# MesschieberBackup.net
KiCad netlist of a schematic drawn in EAGLE
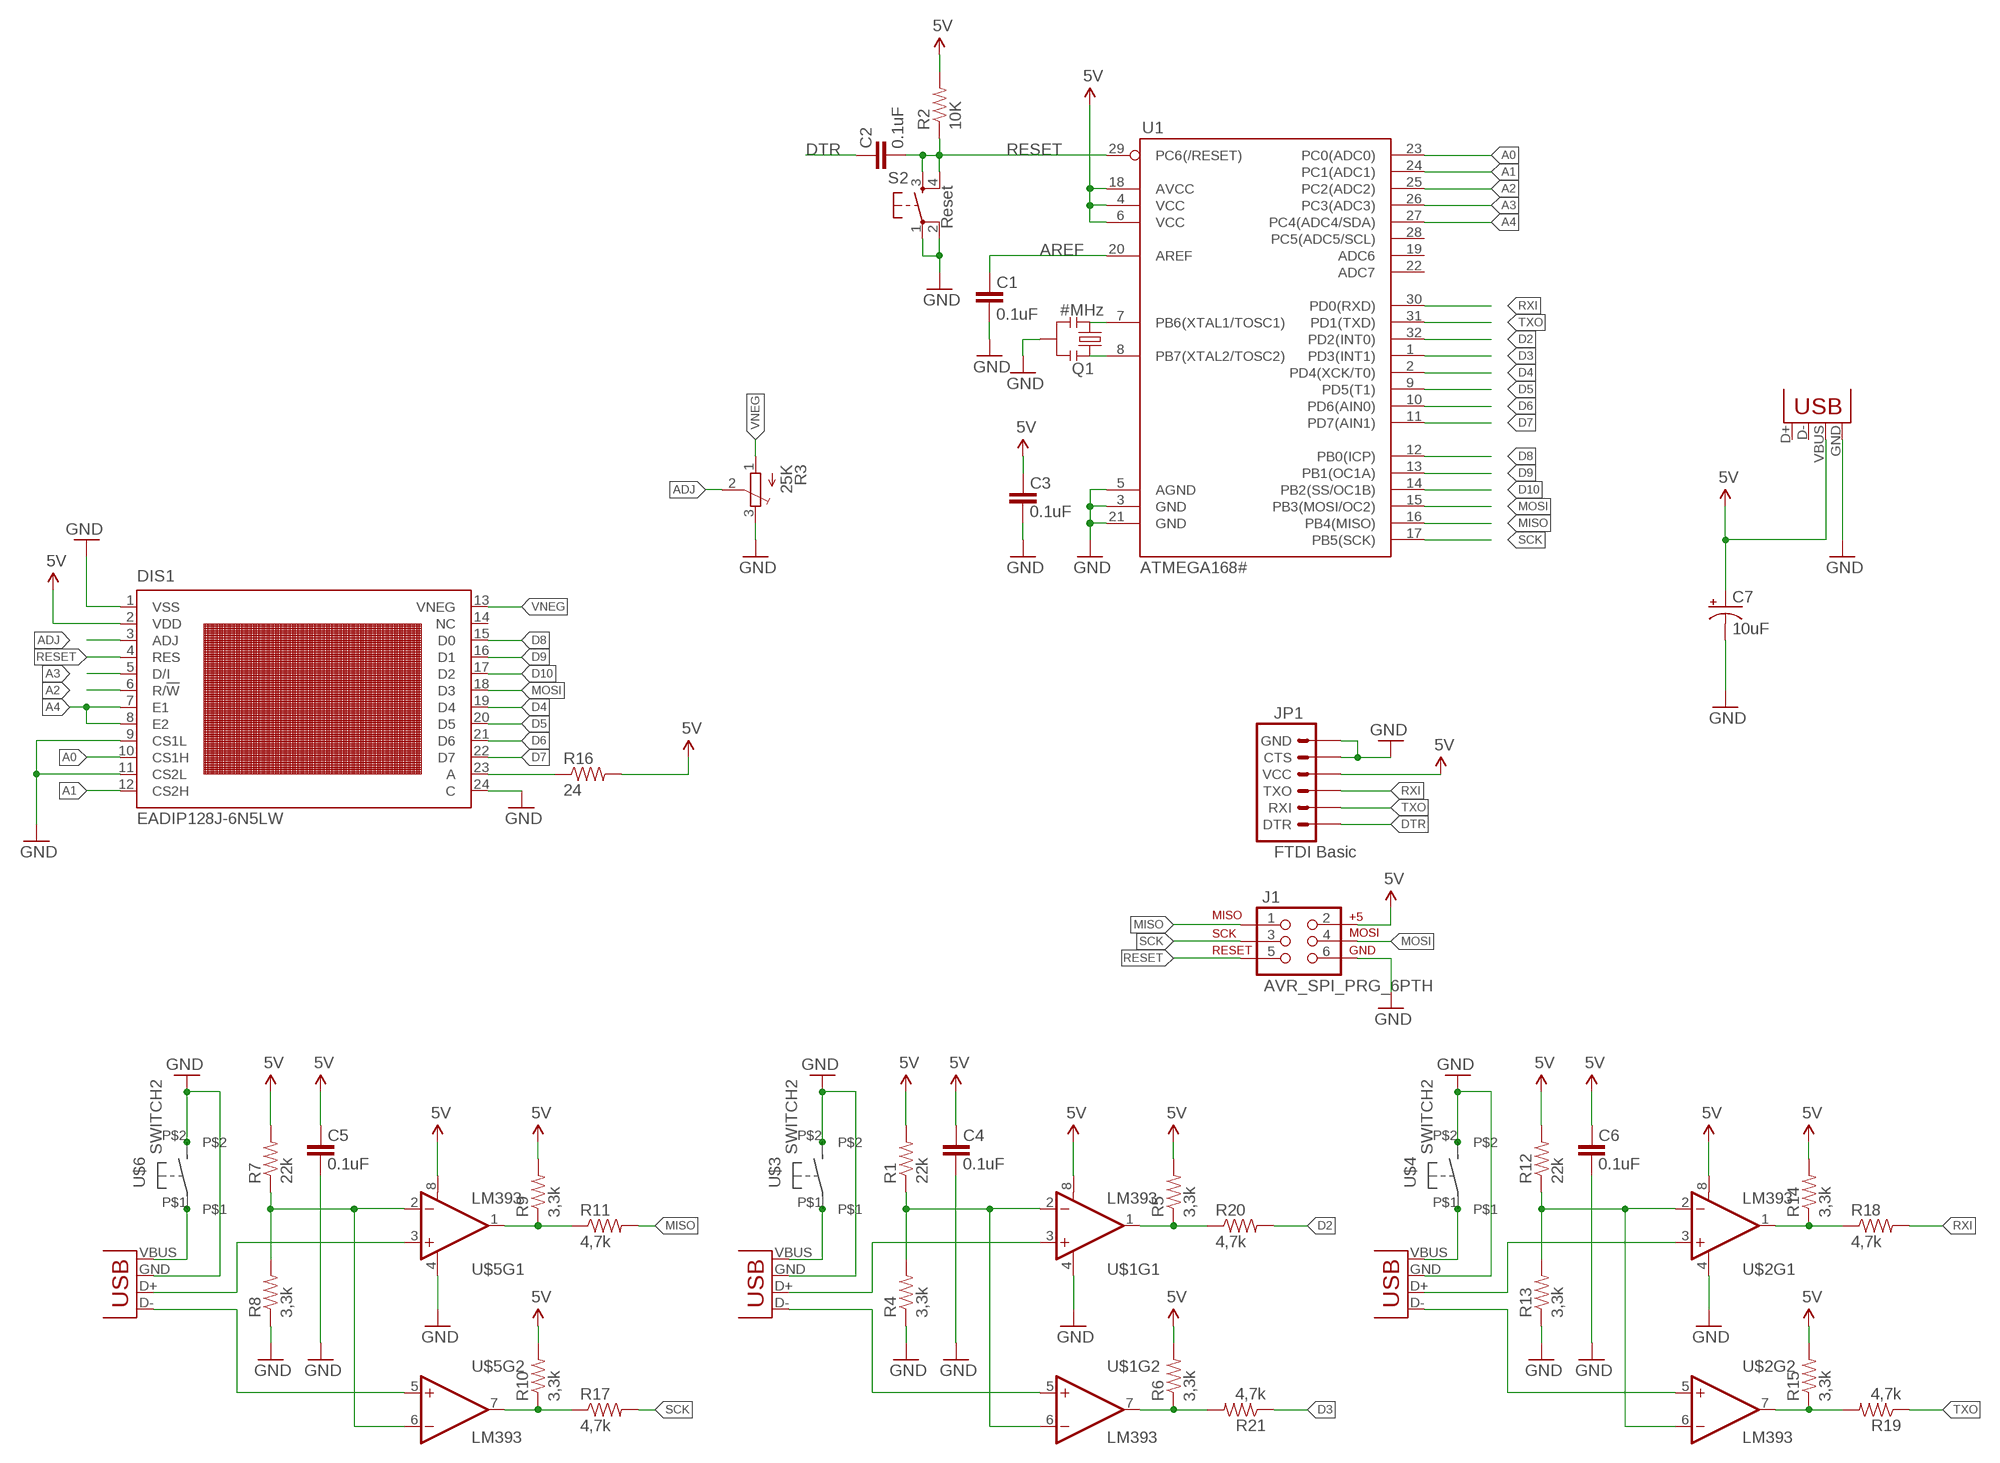
[diagram p0: schematic, sheet 1]

(export (version "E")
  (design (tool "Eeschema 10.0.6"))
  (components
    (comp (ref "C1")
      (value "0.1uF")
      (footprint "eagle-import:0805")
      (libsource (lib "eagle-import") (part "CAP0805"))
    )
    (comp (ref "C2")
      (value "0.1uF")
      (footprint "eagle-import:0805")
      (libsource (lib "eagle-import") (part "CAP0805"))
    )
    (comp (ref "C3")
      (value "0.1uF")
      (footprint "eagle-import:0805")
      (libsource (lib "eagle-import") (part "CAP0805"))
    )
    (comp (ref "C4")
      (value "0.1uF")
      (footprint "eagle-import:0805")
      (libsource (lib "eagle-import") (part "CAP0805"))
    )
    (comp (ref "C5")
      (value "0.1uF")
      (footprint "eagle-import:0805")
      (libsource (lib "eagle-import") (part "CAP0805"))
    )
    (comp (ref "C6")
      (value "0.1uF")
      (footprint "eagle-import:0805")
      (libsource (lib "eagle-import") (part "CAP0805"))
    )
    (comp (ref "C7")
      (value "10uF")
      (footprint "eagle-import:EIA3216")
      (libsource (lib "eagle-import") (part "10UF-16V-10%(TANT)"))
    )
    (comp (ref "DIS1")
      (value "EADIP128J-6N5LW")
      (footprint "eagle-import:LCD-DIP128-64")
      (libsource (lib "eagle-import") (part "EADIP128-6N5LWJ"))
    )
    (comp (ref "J1")
      (value "AVR_SPI_PRG_6PTH")
      (footprint "eagle-import:2X3")
      (libsource (lib "eagle-import") (part "AVR_SPI_PRG_6PTH"))
    )
    (comp (ref "JP1")
      (value "FTDI Basic")
      (footprint "eagle-import:1X06")
      (libsource (lib "eagle-import") (part "ARDUINO_SERIAL_PROGRAMPTH"))
    )
    (comp (ref "JP2")
      (value "USB-A-H")
      (footprint "eagle-import:USB-A-H")
      (libsource (lib "eagle-import") (part "USB-A-H"))
    )
    (comp (ref "JP3")
      (value "USB-A-H")
      (footprint "eagle-import:USB-A-H")
      (libsource (lib "eagle-import") (part "USB-A-H"))
    )
    (comp (ref "JP6")
      (value "USB-A-H")
      (footprint "eagle-import:USB-A-H")
      (libsource (lib "eagle-import") (part "USB-A-H"))
    )
    (comp (ref "JP7")
      (value "USB-SMD-NS")
      (footprint "eagle-import:USB-MINIB-NOSTOP")
      (libsource (lib "eagle-import") (part "USB-SMD-NS"))
    )
    (comp (ref "Q1")
      (value "#MHz")
      (footprint "eagle-import:RESONATOR-SMD")
      (libsource (lib "eagle-import") (part "RESONATORSMD"))
    )
    (comp (ref "R1")
      (value "22k")
      (footprint "eagle-import:0805")
      (libsource (lib "eagle-import") (part "RESISTOR"))
    )
    (comp (ref "R2")
      (value "10K")
      (footprint "eagle-import:0805")
      (libsource (lib "eagle-import") (part "RESISTOR"))
    )
    (comp (ref "R3")
      (value "25K")
      (footprint "eagle-import:SM-42_43A")
      (libsource (lib "eagle-import") (part "TRIM_EU-SM-42/43A"))
    )
    (comp (ref "R4")
      (value "3,3k")
      (footprint "eagle-import:0805")
      (libsource (lib "eagle-import") (part "RESISTOR"))
    )
    (comp (ref "R5")
      (value "3,3k")
      (footprint "eagle-import:0805")
      (libsource (lib "eagle-import") (part "RESISTOR"))
    )
    (comp (ref "R6")
      (value "3,3k")
      (footprint "eagle-import:0805")
      (libsource (lib "eagle-import") (part "RESISTOR"))
    )
    (comp (ref "R7")
      (value "22k")
      (footprint "eagle-import:0805")
      (libsource (lib "eagle-import") (part "RESISTOR"))
    )
    (comp (ref "R8")
      (value "3,3k")
      (footprint "eagle-import:0805")
      (libsource (lib "eagle-import") (part "RESISTOR"))
    )
    (comp (ref "R9")
      (value "3,3k")
      (footprint "eagle-import:0805")
      (libsource (lib "eagle-import") (part "RESISTOR"))
    )
    (comp (ref "R10")
      (value "3,3k")
      (footprint "eagle-import:0805")
      (libsource (lib "eagle-import") (part "RESISTOR"))
    )
    (comp (ref "R11")
      (value "4,7k")
      (footprint "eagle-import:0805")
      (libsource (lib "eagle-import") (part "RESISTOR"))
    )
    (comp (ref "R12")
      (value "22k")
      (footprint "eagle-import:0805")
      (libsource (lib "eagle-import") (part "RESISTOR"))
    )
    (comp (ref "R13")
      (value "3,3k")
      (footprint "eagle-import:0805")
      (libsource (lib "eagle-import") (part "RESISTOR"))
    )
    (comp (ref "R14")
      (value "3,3k")
      (footprint "eagle-import:0805")
      (libsource (lib "eagle-import") (part "RESISTOR"))
    )
    (comp (ref "R15")
      (value "3,3k")
      (footprint "eagle-import:0805")
      (libsource (lib "eagle-import") (part "RESISTOR"))
    )
    (comp (ref "R16")
      (value "24")
      (footprint "eagle-import:0805")
      (libsource (lib "eagle-import") (part "RESISTOR"))
    )
    (comp (ref "R17")
      (value "4,7k")
      (footprint "eagle-import:0805")
      (libsource (lib "eagle-import") (part "RESISTOR"))
    )
    (comp (ref "R18")
      (value "4,7k")
      (footprint "eagle-import:0805")
      (libsource (lib "eagle-import") (part "RESISTOR"))
    )
    (comp (ref "R19")
      (value "4,7k")
      (footprint "eagle-import:0805")
      (libsource (lib "eagle-import") (part "RESISTOR"))
    )
    (comp (ref "R20")
      (value "4,7k")
      (footprint "eagle-import:0805")
      (libsource (lib "eagle-import") (part "RESISTOR"))
    )
    (comp (ref "R21")
      (value "4,7k")
      (footprint "eagle-import:0805")
      (libsource (lib "eagle-import") (part "RESISTOR"))
    )
    (comp (ref "S2")
      (value "Reset")
      (footprint "eagle-import:TACTILE_SWITCH_SMD")
      (libsource (lib "eagle-import") (part "TAC_SWITCHSND"))
    )
    (comp (ref "U$1")
      (value "LM393")
      (footprint "eagle-import:SO08")
      (libsource (lib "eagle-import") (part "LM393"))
    )
    (comp (ref "U$2")
      (value "LM393")
      (footprint "eagle-import:SO08")
      (libsource (lib "eagle-import") (part "LM393"))
    )
    (comp (ref "U$3")
      (value "SWITCH2")
      (footprint "eagle-import:SWITCH2")
      (libsource (lib "eagle-import") (part "SWITCH2"))
    )
    (comp (ref "U$4")
      (value "SWITCH2")
      (footprint "eagle-import:SWITCH2")
      (libsource (lib "eagle-import") (part "SWITCH2"))
    )
    (comp (ref "U$5")
      (value "LM393")
      (footprint "eagle-import:SO08")
      (libsource (lib "eagle-import") (part "LM393"))
    )
    (comp (ref "U$6")
      (value "SWITCH2")
      (footprint "eagle-import:SWITCH2")
      (libsource (lib "eagle-import") (part "SWITCH2"))
    )
    (comp (ref "U1")
      (value "ATMEGA168#")
      (footprint "eagle-import:TQFP32-08")
      (libsource (lib "eagle-import") (part "ATMEGA168"))
    )
  )
  (nets
    (net (code "1") (name "/AREF") (class "Default")
      (node (ref "C1") (pin "2") (pinfunction "2_2") (pintype "passive"))
      (node (ref "U1") (pin "20") (pinfunction "AREF_20") (pintype "bidirectional"))
    )
    (net (code "2") (name "5V") (class "Default")
      (node (ref "C3") (pin "2") (pinfunction "2_2") (pintype "passive"))
      (node (ref "C4") (pin "2") (pinfunction "2_2") (pintype "passive"))
      (node (ref "C5") (pin "2") (pinfunction "2_2") (pintype "passive"))
      (node (ref "C6") (pin "2") (pinfunction "2_2") (pintype "passive"))
      (node (ref "C7") (pin "A") (pinfunction "+_A") (pintype "passive"))
      (node (ref "DIS1") (pin "2") (pinfunction "VDD_2") (pintype "power_in"))
      (node (ref "J1") (pin "2") (pinfunction "2_2") (pintype "passive"))
      (node (ref "JP1") (pin "4") (pinfunction "VCC_4") (pintype "passive"))
      (node (ref "JP7") (pin "VBUS") (pinfunction "VBUS_VBUS") (pintype "bidirectional"))
      (node (ref "R1") (pin "2") (pinfunction "2_2") (pintype "passive"))
      (node (ref "R10") (pin "2") (pinfunction "2_2") (pintype "passive"))
      (node (ref "R12") (pin "2") (pinfunction "2_2") (pintype "passive"))
      (node (ref "R14") (pin "2") (pinfunction "2_2") (pintype "passive"))
      (node (ref "R15") (pin "2") (pinfunction "2_2") (pintype "passive"))
      (node (ref "R16") (pin "2") (pinfunction "2_2") (pintype "passive"))
      (node (ref "R2") (pin "2") (pinfunction "2_2") (pintype "passive"))
      (node (ref "R5") (pin "2") (pinfunction "2_2") (pintype "passive"))
      (node (ref "R6") (pin "2") (pinfunction "2_2") (pintype "passive"))
      (node (ref "R7") (pin "2") (pinfunction "2_2") (pintype "passive"))
      (node (ref "R9") (pin "2") (pinfunction "2_2") (pintype "passive"))
      (node (ref "U$1") (pin "8") (pinfunction "V+_8") (pintype "power_in"))
      (node (ref "U$2") (pin "8") (pinfunction "V+_8") (pintype "power_in"))
      (node (ref "U$5") (pin "8") (pinfunction "V+_8") (pintype "power_in"))
      (node (ref "U1") (pin "18") (pinfunction "AVCC_18") (pintype "bidirectional"))
      (node (ref "U1") (pin "4") (pinfunction "VCC_4") (pintype "bidirectional"))
      (node (ref "U1") (pin "6") (pinfunction "VCC_6") (pintype "bidirectional"))
    )
    (net (code "3") (name "A0") (class "Default")
      (node (ref "DIS1") (pin "10") (pinfunction "CS1H_10") (pintype "input"))
      (node (ref "U1") (pin "23") (pinfunction "PC0(ADC0)_23") (pintype "bidirectional"))
    )
    (net (code "4") (name "A1") (class "Default")
      (node (ref "DIS1") (pin "12") (pinfunction "CS2H_12") (pintype "input"))
      (node (ref "U1") (pin "24") (pinfunction "PC1(ADC1)_24") (pintype "bidirectional"))
    )
    (net (code "5") (name "A2") (class "Default")
      (node (ref "DIS1") (pin "6") (pinfunction "R/~{W}_6") (pintype "input"))
      (node (ref "U1") (pin "25") (pinfunction "PC2(ADC2)_25") (pintype "bidirectional"))
    )
    (net (code "6") (name "A3") (class "Default")
      (node (ref "DIS1") (pin "5") (pinfunction "D/I_5") (pintype "input"))
      (node (ref "U1") (pin "26") (pinfunction "PC3(ADC3)_26") (pintype "bidirectional"))
    )
    (net (code "7") (name "A4") (class "Default")
      (node (ref "DIS1") (pin "7") (pinfunction "E1_7") (pintype "input"))
      (node (ref "DIS1") (pin "8") (pinfunction "E2_8") (pintype "input"))
      (node (ref "U1") (pin "27") (pinfunction "PC4(ADC4/SDA)_27") (pintype "bidirectional"))
    )
    (net (code "8") (name "ADJ") (class "Default")
      (node (ref "DIS1") (pin "3") (pinfunction "ADJ_3") (pintype "input"))
      (node (ref "R3") (pin "2") (pinfunction "S_2") (pintype "passive"))
    )
    (net (code "9") (name "D2") (class "Default")
      (node (ref "R20") (pin "2") (pinfunction "2_2") (pintype "passive"))
      (node (ref "U1") (pin "32") (pinfunction "PD2(INT0)_32") (pintype "bidirectional"))
    )
    (net (code "10") (name "D3") (class "Default")
      (node (ref "R21") (pin "1") (pinfunction "1_1") (pintype "passive"))
      (node (ref "U1") (pin "1") (pinfunction "PD3(INT1)_1") (pintype "bidirectional"))
    )
    (net (code "11") (name "D4") (class "Default")
      (node (ref "DIS1") (pin "19") (pinfunction "D4_19") (pintype "bidirectional"))
      (node (ref "U1") (pin "2") (pinfunction "PD4(XCK/T0)_2") (pintype "bidirectional"))
    )
    (net (code "12") (name "D5") (class "Default")
      (node (ref "DIS1") (pin "20") (pinfunction "D5_20") (pintype "bidirectional"))
      (node (ref "U1") (pin "9") (pinfunction "PD5(T1)_9") (pintype "bidirectional"))
    )
    (net (code "13") (name "D6") (class "Default")
      (node (ref "DIS1") (pin "21") (pinfunction "D6_21") (pintype "bidirectional"))
      (node (ref "U1") (pin "10") (pinfunction "PD6(AIN0)_10") (pintype "bidirectional"))
    )
    (net (code "14") (name "D7") (class "Default")
      (node (ref "DIS1") (pin "22") (pinfunction "D7_22") (pintype "bidirectional"))
      (node (ref "U1") (pin "11") (pinfunction "PD7(AIN1)_11") (pintype "bidirectional"))
    )
    (net (code "15") (name "D8") (class "Default")
      (node (ref "DIS1") (pin "15") (pinfunction "D0_15") (pintype "bidirectional"))
      (node (ref "U1") (pin "12") (pinfunction "PB0(ICP)_12") (pintype "bidirectional"))
    )
    (net (code "16") (name "D9") (class "Default")
      (node (ref "DIS1") (pin "16") (pinfunction "D1_16") (pintype "bidirectional"))
      (node (ref "U1") (pin "13") (pinfunction "PB1(OC1A)_13") (pintype "bidirectional"))
    )
    (net (code "17") (name "D10") (class "Default")
      (node (ref "DIS1") (pin "17") (pinfunction "D2_17") (pintype "bidirectional"))
      (node (ref "U1") (pin "14") (pinfunction "PB2(SS/OC1B)_14") (pintype "bidirectional"))
    )
    (net (code "18") (name "DTR") (class "Default")
      (node (ref "C2") (pin "2") (pinfunction "2_2") (pintype "passive"))
      (node (ref "JP1") (pin "1") (pinfunction "DTR_1") (pintype "passive"))
    )
    (net (code "19") (name "GND") (class "Default")
      (node (ref "C1") (pin "1") (pinfunction "1_1") (pintype "passive"))
      (node (ref "C3") (pin "1") (pinfunction "1_1") (pintype "passive"))
      (node (ref "C4") (pin "1") (pinfunction "1_1") (pintype "passive"))
      (node (ref "C5") (pin "1") (pinfunction "1_1") (pintype "passive"))
      (node (ref "C6") (pin "1") (pinfunction "1_1") (pintype "passive"))
      (node (ref "C7") (pin "C") (pinfunction "-_C") (pintype "passive"))
      (node (ref "DIS1") (pin "1") (pinfunction "VSS_1") (pintype "power_in"))
      (node (ref "DIS1") (pin "11") (pinfunction "CS2L_11") (pintype "input"))
      (node (ref "DIS1") (pin "24") (pinfunction "C_24") (pintype "passive"))
      (node (ref "DIS1") (pin "9") (pinfunction "CS1L_9") (pintype "input"))
      (node (ref "J1") (pin "6") (pinfunction "6_6") (pintype "passive"))
      (node (ref "JP1") (pin "5") (pinfunction "CTS_5") (pintype "passive"))
      (node (ref "JP1") (pin "6") (pinfunction "GND_6") (pintype "passive"))
      (node (ref "JP2") (pin "GND") (pinfunction "VBUS_GND") (pintype "bidirectional"))
      (node (ref "JP3") (pin "GND") (pinfunction "VBUS_GND") (pintype "bidirectional"))
      (node (ref "JP6") (pin "GND") (pinfunction "VBUS_GND") (pintype "bidirectional"))
      (node (ref "JP7") (pin "GND") (pinfunction "GND_GND") (pintype "bidirectional"))
      (node (ref "Q1") (pin "2") (pinfunction "2_2") (pintype "passive"))
      (node (ref "R13") (pin "1") (pinfunction "1_1") (pintype "passive"))
      (node (ref "R3") (pin "3") (pinfunction "E_3") (pintype "passive"))
      (node (ref "R4") (pin "1") (pinfunction "1_1") (pintype "passive"))
      (node (ref "R8") (pin "1") (pinfunction "1_1") (pintype "passive"))
      (node (ref "S2") (pin "1") (pinfunction "1_1") (pintype "passive"))
      (node (ref "S2") (pin "2") (pinfunction "2_2") (pintype "passive"))
      (node (ref "U$1") (pin "4") (pinfunction "V-_4") (pintype "power_in"))
      (node (ref "U$2") (pin "4") (pinfunction "V-_4") (pintype "power_in"))
      (node (ref "U$3") (pin "P$2") (pinfunction "P$2_P$2") (pintype "bidirectional"))
      (node (ref "U$4") (pin "P$2") (pinfunction "P$2_P$2") (pintype "bidirectional"))
      (node (ref "U$5") (pin "4") (pinfunction "V-_4") (pintype "power_in"))
      (node (ref "U$6") (pin "P$2") (pinfunction "P$2_P$2") (pintype "bidirectional"))
      (node (ref "U1") (pin "21") (pinfunction "GND_21") (pintype "bidirectional"))
      (node (ref "U1") (pin "3") (pinfunction "GND_3") (pintype "bidirectional"))
      (node (ref "U1") (pin "5") (pinfunction "AGND_5") (pintype "bidirectional"))
    )
    (net (code "20") (name "MISO") (class "Default")
      (node (ref "J1") (pin "1") (pinfunction "1_1") (pintype "passive"))
      (node (ref "R11") (pin "2") (pinfunction "2_2") (pintype "passive"))
      (node (ref "U1") (pin "16") (pinfunction "PB4(MISO)_16") (pintype "bidirectional"))
    )
    (net (code "21") (name "MOSI") (class "Default")
      (node (ref "DIS1") (pin "18") (pinfunction "D3_18") (pintype "bidirectional"))
      (node (ref "J1") (pin "4") (pinfunction "4_4") (pintype "passive"))
      (node (ref "U1") (pin "15") (pinfunction "PB3(MOSI/OC2)_15") (pintype "bidirectional"))
    )
    (net (code "22") (name "Net-(DIS1-A)") (class "Default")
      (node (ref "DIS1") (pin "23") (pinfunction "A_23") (pintype "passive"))
      (node (ref "R16") (pin "1") (pinfunction "1_1") (pintype "passive"))
    )
    (net (code "23") (name "Net-(JP2-D+)") (class "Default")
      (node (ref "JP2") (pin "D-") (pinfunction "D+_D-") (pintype "bidirectional"))
      (node (ref "U$1") (pin "5") (pinfunction "+IN_5") (pintype "input"))
    )
    (net (code "24") (name "Net-(JP2-D-)") (class "Default")
      (node (ref "JP2") (pin "D+") (pinfunction "D-_D+") (pintype "bidirectional"))
      (node (ref "U$1") (pin "3") (pinfunction "+IN_3") (pintype "input"))
    )
    (net (code "25") (name "Net-(JP2-GND)") (class "Default")
      (node (ref "JP2") (pin "VBUS") (pinfunction "GND_VBUS") (pintype "bidirectional"))
      (node (ref "U$3") (pin "P$1") (pinfunction "P$1_P$1") (pintype "bidirectional"))
    )
    (net (code "26") (name "Net-(JP3-D+)") (class "Default")
      (node (ref "JP3") (pin "D-") (pinfunction "D+_D-") (pintype "bidirectional"))
      (node (ref "U$5") (pin "5") (pinfunction "+IN_5") (pintype "input"))
    )
    (net (code "27") (name "Net-(JP3-D-)") (class "Default")
      (node (ref "JP3") (pin "D+") (pinfunction "D-_D+") (pintype "bidirectional"))
      (node (ref "U$5") (pin "3") (pinfunction "+IN_3") (pintype "input"))
    )
    (net (code "28") (name "Net-(JP3-GND)") (class "Default")
      (node (ref "JP3") (pin "VBUS") (pinfunction "GND_VBUS") (pintype "bidirectional"))
      (node (ref "U$6") (pin "P$1") (pinfunction "P$1_P$1") (pintype "bidirectional"))
    )
    (net (code "29") (name "Net-(JP6-D+)") (class "Default")
      (node (ref "JP6") (pin "D-") (pinfunction "D+_D-") (pintype "bidirectional"))
      (node (ref "U$2") (pin "5") (pinfunction "+IN_5") (pintype "input"))
    )
    (net (code "30") (name "Net-(JP6-D-)") (class "Default")
      (node (ref "JP6") (pin "D+") (pinfunction "D-_D+") (pintype "bidirectional"))
      (node (ref "U$2") (pin "3") (pinfunction "+IN_3") (pintype "input"))
    )
    (net (code "31") (name "Net-(JP6-GND)") (class "Default")
      (node (ref "JP6") (pin "VBUS") (pinfunction "GND_VBUS") (pintype "bidirectional"))
      (node (ref "U$4") (pin "P$1") (pinfunction "P$1_P$1") (pintype "bidirectional"))
    )
    (net (code "32") (name "Net-(U$1A--IN)") (class "Default")
      (node (ref "R1") (pin "1") (pinfunction "1_1") (pintype "passive"))
      (node (ref "R4") (pin "2") (pinfunction "2_2") (pintype "passive"))
      (node (ref "U$1") (pin "2") (pinfunction "-IN_2") (pintype "input"))
      (node (ref "U$1") (pin "6") (pinfunction "-IN_6") (pintype "input"))
    )
    (net (code "33") (name "Net-(U$1A-OUT)") (class "Default")
      (node (ref "R20") (pin "1") (pinfunction "1_1") (pintype "passive"))
      (node (ref "R5") (pin "1") (pinfunction "1_1") (pintype "passive"))
      (node (ref "U$1") (pin "1") (pinfunction "OUT_1") (pintype "output"))
    )
    (net (code "34") (name "Net-(U$1B-OUT)") (class "Default")
      (node (ref "R21") (pin "2") (pinfunction "2_2") (pintype "passive"))
      (node (ref "R6") (pin "1") (pinfunction "1_1") (pintype "passive"))
      (node (ref "U$1") (pin "7") (pinfunction "OUT_7") (pintype "output"))
    )
    (net (code "35") (name "Net-(U$2A--IN)") (class "Default")
      (node (ref "R12") (pin "1") (pinfunction "1_1") (pintype "passive"))
      (node (ref "R13") (pin "2") (pinfunction "2_2") (pintype "passive"))
      (node (ref "U$2") (pin "2") (pinfunction "-IN_2") (pintype "input"))
      (node (ref "U$2") (pin "6") (pinfunction "-IN_6") (pintype "input"))
    )
    (net (code "36") (name "Net-(U$2A-OUT)") (class "Default")
      (node (ref "R14") (pin "1") (pinfunction "1_1") (pintype "passive"))
      (node (ref "R18") (pin "1") (pinfunction "1_1") (pintype "passive"))
      (node (ref "U$2") (pin "1") (pinfunction "OUT_1") (pintype "output"))
    )
    (net (code "37") (name "Net-(U$2B-OUT)") (class "Default")
      (node (ref "R15") (pin "1") (pinfunction "1_1") (pintype "passive"))
      (node (ref "R19") (pin "2") (pinfunction "2_2") (pintype "passive"))
      (node (ref "U$2") (pin "7") (pinfunction "OUT_7") (pintype "output"))
    )
    (net (code "38") (name "Net-(U$5A--IN)") (class "Default")
      (node (ref "R7") (pin "1") (pinfunction "1_1") (pintype "passive"))
      (node (ref "R8") (pin "2") (pinfunction "2_2") (pintype "passive"))
      (node (ref "U$5") (pin "2") (pinfunction "-IN_2") (pintype "input"))
      (node (ref "U$5") (pin "6") (pinfunction "-IN_6") (pintype "input"))
    )
    (net (code "39") (name "Net-(U$5A-OUT)") (class "Default")
      (node (ref "R11") (pin "1") (pinfunction "1_1") (pintype "passive"))
      (node (ref "R9") (pin "1") (pinfunction "1_1") (pintype "passive"))
      (node (ref "U$5") (pin "1") (pinfunction "OUT_1") (pintype "output"))
    )
    (net (code "40") (name "Net-(U$5B-OUT)") (class "Default")
      (node (ref "R10") (pin "1") (pinfunction "1_1") (pintype "passive"))
      (node (ref "R17") (pin "1") (pinfunction "1_1") (pintype "passive"))
      (node (ref "U$5") (pin "7") (pinfunction "OUT_7") (pintype "output"))
    )
    (net (code "41") (name "Net-(U1-PB6(XTAL1{slash}TOSC1))") (class "Default")
      (node (ref "Q1") (pin "3") (pinfunction "3_3") (pintype "passive"))
      (node (ref "U1") (pin "7") (pinfunction "PB6(XTAL1/TOSC1)_7") (pintype "bidirectional"))
    )
    (net (code "42") (name "Net-(U1-PB7(XTAL2{slash}TOSC2))") (class "Default")
      (node (ref "Q1") (pin "1") (pinfunction "1_1") (pintype "passive"))
      (node (ref "U1") (pin "8") (pinfunction "PB7(XTAL2/TOSC2)_8") (pintype "bidirectional"))
    )
    (net (code "43") (name "RESET") (class "Default")
      (node (ref "C2") (pin "1") (pinfunction "1_1") (pintype "passive"))
      (node (ref "DIS1") (pin "4") (pinfunction "RES_4") (pintype "input"))
      (node (ref "J1") (pin "5") (pinfunction "5_5") (pintype "passive"))
      (node (ref "R2") (pin "1") (pinfunction "1_1") (pintype "passive"))
      (node (ref "S2") (pin "3") (pinfunction "3_3") (pintype "passive"))
      (node (ref "S2") (pin "4") (pinfunction "4_4") (pintype "passive"))
      (node (ref "U1") (pin "29") (pinfunction "PC6(/RESET)_29") (pintype "bidirectional"))
    )
    (net (code "44") (name "RXI") (class "Default")
      (node (ref "JP1") (pin "3") (pinfunction "TXO_3") (pintype "passive"))
      (node (ref "R18") (pin "2") (pinfunction "2_2") (pintype "passive"))
      (node (ref "U1") (pin "30") (pinfunction "PD0(RXD)_30") (pintype "bidirectional"))
    )
    (net (code "45") (name "SCK") (class "Default")
      (node (ref "J1") (pin "3") (pinfunction "3_3") (pintype "passive"))
      (node (ref "R17") (pin "2") (pinfunction "2_2") (pintype "passive"))
      (node (ref "U1") (pin "17") (pinfunction "PB5(SCK)_17") (pintype "bidirectional"))
    )
    (net (code "46") (name "TXO") (class "Default")
      (node (ref "JP1") (pin "2") (pinfunction "RXI_2") (pintype "passive"))
      (node (ref "R19") (pin "1") (pinfunction "1_1") (pintype "passive"))
      (node (ref "U1") (pin "31") (pinfunction "PD1(TXD)_31") (pintype "bidirectional"))
    )
    (net (code "47") (name "VNEG") (class "Default")
      (node (ref "DIS1") (pin "13") (pinfunction "VNEG_13") (pintype "passive"))
      (node (ref "R3") (pin "1") (pinfunction "A_1") (pintype "passive"))
    )
    (net (code "48") (name "unconnected-(DIS1-NC-Pad14)") (class "Default")
      (node (ref "DIS1") (pin "14") (pinfunction "NC_14") (pintype "no_connect"))
    )
    (net (code "49") (name "unconnected-(JP7-PadD+)") (class "Default")
      (node (ref "JP7") (pin "D+") (pinfunction "D+_D+") (pintype "bidirectional"))
    )
    (net (code "50") (name "unconnected-(JP7-PadD-)") (class "Default")
      (node (ref "JP7") (pin "D-") (pinfunction "D-_D-") (pintype "bidirectional"))
    )
    (net (code "51") (name "unconnected-(U1-ADC6-Pad19)") (class "Default")
      (node (ref "U1") (pin "19") (pinfunction "ADC6_19") (pintype "bidirectional"))
    )
    (net (code "52") (name "unconnected-(U1-ADC7-Pad22)") (class "Default")
      (node (ref "U1") (pin "22") (pinfunction "ADC7_22") (pintype "bidirectional"))
    )
    (net (code "53") (name "unconnected-(U1-PC5(ADC5{slash}SCL)-Pad28)") (class "Default")
      (node (ref "U1") (pin "28") (pinfunction "PC5(ADC5/SCL)_28") (pintype "bidirectional"))
    )
  )
)
